# Sheet1.net
KiCad netlist of a schematic drawn in Altium Designer
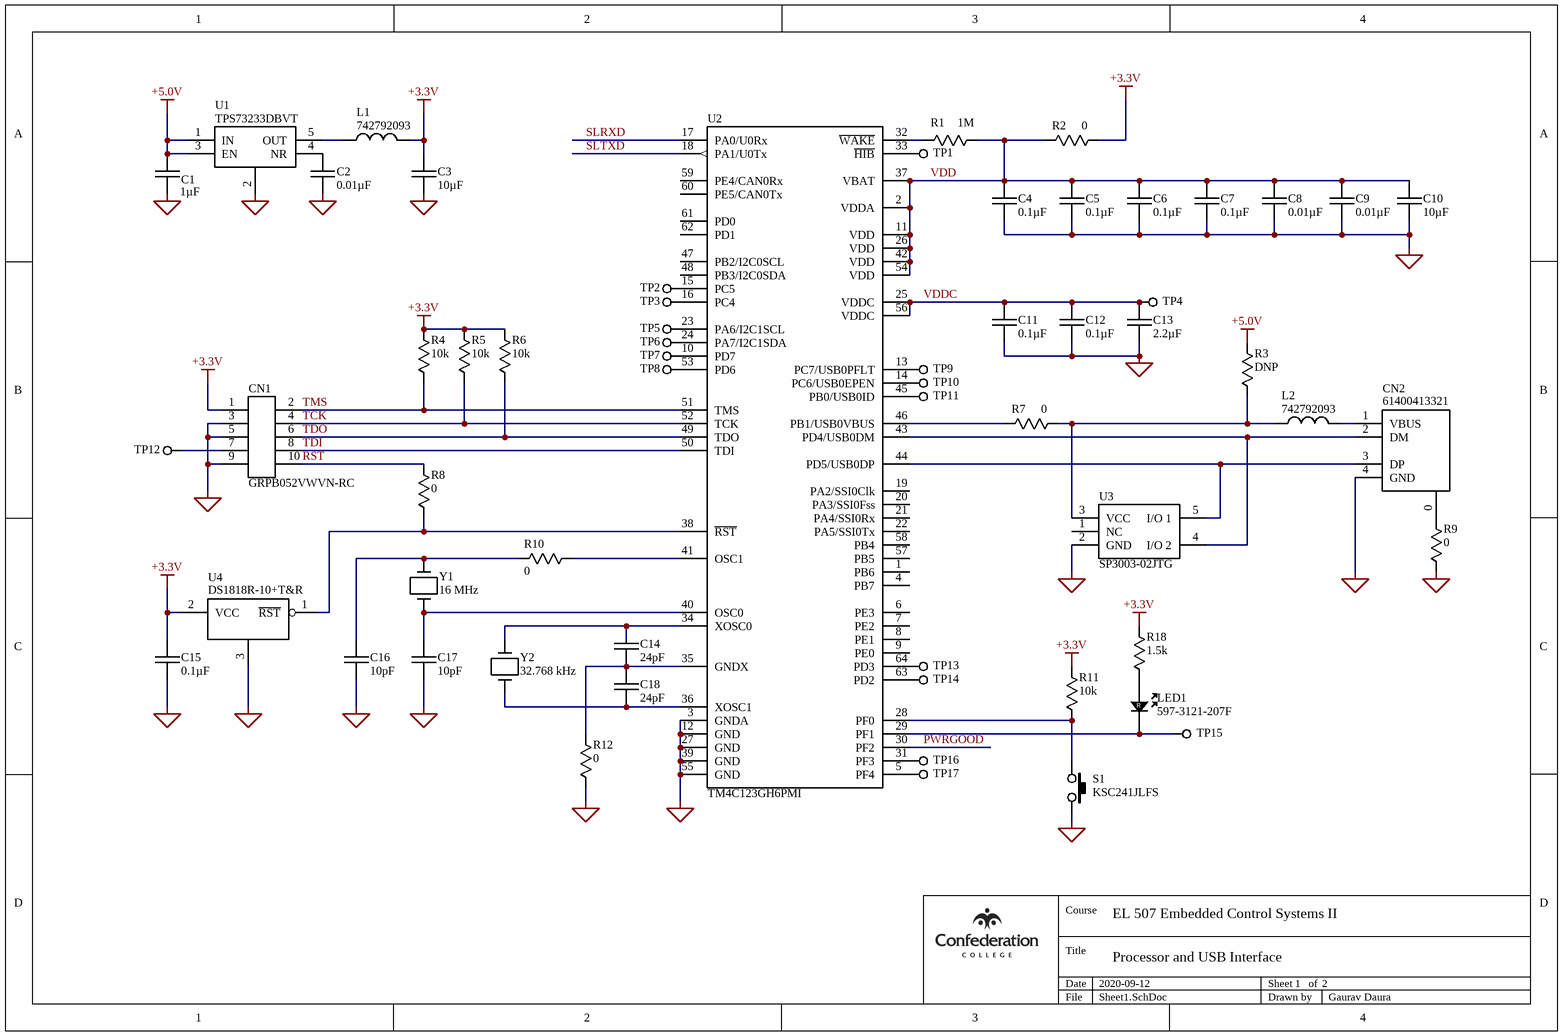
[diagram p0: Sheet1.SchDoc]

(export (version "E")
  (design (tool "Eeschema 10.0.6"))
  (components
    (comp (ref "C1")
      (value "1µF")
      (footprint "CAPC2012X135N")
      (description "1µF/50V 10% X7R Multi-Layer Ceramic Capacitor")
      (fields
        (field (name "MANUFACTURER") "Samsung Electro-Mechanics")
        (field (name "PARTNUMBER") "CL21B105KBFNNNE")
      )
      (libsource (lib "EL507-LAB001") (part "CL21B105KBFNNNE"))
    )
    (comp (ref "C2")
      (value "0.01µF")
      (footprint "CAPC2012X78N")
      (description "0.01µF/50V 10% X7R Multi-Layer Ceramic Capacitor")
      (fields
        (field (name "MANUFACTURER") "Samsung Electro-Mechanics")
        (field (name "PARTNUMBER") "CL21B103KBANNNC")
      )
      (libsource (lib "EL507-LAB001") (part "CL21B103KBANNNC"))
    )
    (comp (ref "C3")
      (value "10µF")
      (footprint "CAPC3225X250N")
      (description "10µF/50V/20% Multilayer Ceramic Chip Capacitor")
      (fields (field (name "MANUFACTURER") "Taiyo Yuden") (field (name "PARTNUMBER") "UMK325C7106MM-T"))
      (libsource (lib "EL507-LAB001") (part "UMK325C7106MM-T"))
    )
    (comp (ref "C4")
      (value "0.1µF")
      (footprint "CAPC2012X125N")
      (description "0.1µF/50V/±10% X7R Ceramic Chip Capacitor")
      (fields
        (field (name "MANUFACTURER") "Murata Manufacturing Co., Ltd.")
        (field (name "PARTNUMBER") "GRM21BR71H104KA01L")
      )
      (libsource (lib "EL507-LAB001") (part "GRM21BR71H104KA01L"))
    )
    (comp (ref "C5")
      (value "0.1µF")
      (footprint "CAPC2012X125N")
      (description "0.1µF/50V/±10% X7R Ceramic Chip Capacitor")
      (fields
        (field (name "MANUFACTURER") "Murata Manufacturing Co., Ltd.")
        (field (name "PARTNUMBER") "GRM21BR71H104KA01L")
      )
      (libsource (lib "EL507-LAB001") (part "GRM21BR71H104KA01L"))
    )
    (comp (ref "C6")
      (value "0.1µF")
      (footprint "CAPC2012X125N")
      (description "0.1µF/50V/±10% X7R Ceramic Chip Capacitor")
      (fields
        (field (name "MANUFACTURER") "Murata Manufacturing Co., Ltd.")
        (field (name "PARTNUMBER") "GRM21BR71H104KA01L")
      )
      (libsource (lib "EL507-LAB001") (part "GRM21BR71H104KA01L"))
    )
    (comp (ref "C7")
      (value "0.1µF")
      (footprint "CAPC2012X125N")
      (description "0.1µF/50V/±10% X7R Ceramic Chip Capacitor")
      (fields
        (field (name "MANUFACTURER") "Murata Manufacturing Co., Ltd.")
        (field (name "PARTNUMBER") "GRM21BR71H104KA01L")
      )
      (libsource (lib "EL507-LAB001") (part "GRM21BR71H104KA01L"))
    )
    (comp (ref "C8")
      (value "0.01µF")
      (footprint "CAPC2012X78N")
      (description "0.01µF/50V 10% X7R Multi-Layer Ceramic Capacitor")
      (fields
        (field (name "MANUFACTURER") "Samsung Electro-Mechanics")
        (field (name "PARTNUMBER") "CL21B103KBANNNC")
      )
      (libsource (lib "EL507-LAB001") (part "CL21B103KBANNNC"))
    )
    (comp (ref "C9")
      (value "0.01µF")
      (footprint "CAPC2012X78N")
      (description "0.01µF/50V 10% X7R Multi-Layer Ceramic Capacitor")
      (fields
        (field (name "MANUFACTURER") "Samsung Electro-Mechanics")
        (field (name "PARTNUMBER") "CL21B103KBANNNC")
      )
      (libsource (lib "EL507-LAB001") (part "CL21B103KBANNNC"))
    )
    (comp (ref "C10")
      (value "10µF")
      (footprint "CAPC3225X250N")
      (description "10µF/50V/20% Multilayer Ceramic Chip Capacitor")
      (fields (field (name "MANUFACTURER") "Taiyo Yuden") (field (name "PARTNUMBER") "UMK325C7106MM-T"))
      (libsource (lib "EL507-LAB001") (part "UMK325C7106MM-T"))
    )
    (comp (ref "C11")
      (value "0.1µF")
      (footprint "CAPC2012X125N")
      (description "0.1µF/50V/±10% X7R Ceramic Chip Capacitor")
      (fields
        (field (name "MANUFACTURER") "Murata Manufacturing Co., Ltd.")
        (field (name "PARTNUMBER") "GRM21BR71H104KA01L")
      )
      (libsource (lib "EL507-LAB001") (part "GRM21BR71H104KA01L"))
    )
    (comp (ref "C12")
      (value "0.1µF")
      (footprint "CAPC2012X125N")
      (description "0.1µF/50V/±10% X7R Ceramic Chip Capacitor")
      (fields
        (field (name "MANUFACTURER") "Murata Manufacturing Co., Ltd.")
        (field (name "PARTNUMBER") "GRM21BR71H104KA01L")
      )
      (libsource (lib "EL507-LAB001") (part "GRM21BR71H104KA01L"))
    )
    (comp (ref "C13")
      (value "2.2µF")
      (footprint "CAPC2012X145N")
      (description "2.2µF/50V/10% Multilayer Ceramic Chip Capacitor")
      (fields (field (name "MANUFACTURER") "Taiyo Yuden") (field (name "PARTNUMBER") "UMK212BB7225KG-T"))
      (libsource (lib "EL507-LAB001") (part "UMK212BB7225KG-T"))
    )
    (comp (ref "C14")
      (value "24pF")
      (footprint "CAPC2012X75N")
      (description "24pF/50V 5% C0G Multi-Layer Ceramic Capacitor")
      (fields
        (field (name "MANUFACTURER") "Samsung Electro-Mechanics")
        (field (name "PARTNUMBER") "CL21C240JBANNNC")
      )
      (libsource (lib "EL507-LAB001") (part "CL21C240JBANNNC"))
    )
    (comp (ref "C15")
      (value "0.1µF")
      (footprint "CAPC2012X125N")
      (description "0.1µF/50V/±10% X7R Ceramic Chip Capacitor")
      (fields
        (field (name "MANUFACTURER") "Murata Manufacturing Co., Ltd.")
        (field (name "PARTNUMBER") "GRM21BR71H104KA01L")
      )
      (libsource (lib "EL507-LAB001") (part "GRM21BR71H104KA01L"))
    )
    (comp (ref "C16")
      (value "10pF")
      (footprint "CAPC2012X94N")
      (description "10pF 100V NP0 ±10% Ceramic Capacitor")
      (fields (field (name "MANUFACTURER") "AVX Corporation") (field (name "PARTNUMBER") "08051A100KAT2A"))
      (libsource (lib "EL507-LAB001") (part "08051A100KAT2A"))
    )
    (comp (ref "C17")
      (value "10pF")
      (footprint "CAPC2012X94N")
      (description "10pF 100V NP0 ±10% Ceramic Capacitor")
      (fields (field (name "MANUFACTURER") "AVX Corporation") (field (name "PARTNUMBER") "08051A100KAT2A"))
      (libsource (lib "EL507-LAB001") (part "08051A100KAT2A"))
    )
    (comp (ref "C18")
      (value "24pF")
      (footprint "CAPC2012X75N")
      (description "24pF/50V 5% C0G Multi-Layer Ceramic Capacitor")
      (fields
        (field (name "MANUFACTURER") "Samsung Electro-Mechanics")
        (field (name "PARTNUMBER") "CL21C240JBANNNC")
      )
      (libsource (lib "EL507-LAB001") (part "CL21C240JBANNNC"))
    )
    (comp (ref "CN1")
      (value "GRPB052VWVN-RC")
      (footprint "SULLINS_GRPB052VWVN-RC")
      (description ".050\"[1.27mm] Contact Centers, Male Header")
      (fields (field (name "MANUFACTURER") "Sullins Connector Solutions, Inc."))
      (libsource (lib "EL507-LAB001") (part "GRPB052VWVN-RC"))
    )
    (comp (ref "CN2")
      (value "61400413321")
      (footprint "WURTH_61400413321")
      (description "Connector Receptacle USB Type B 4 Position Through Hole, Vertical")
      (fields (field (name "MANUFACTURER") "Wurth Elektronik GmbH & Co. KG"))
      (libsource (lib "EL507-LAB001") (part "61400413321"))
    )
    (comp (ref "L1")
      (value "742792093")
      (footprint "INDC2012X90N")
      (description "Multilayer SMD Ferrite")
      (fields (field (name "MANUFACTURER") "Wurth Elektronik GmbH & Co. KG"))
      (libsource (lib "EL507-LAB001") (part "742792093"))
    )
    (comp (ref "L2")
      (value "742792093")
      (footprint "INDC2012X90N")
      (description "Multilayer SMD Ferrite")
      (fields (field (name "MANUFACTURER") "Wurth Elektronik GmbH & Co. KG"))
      (libsource (lib "EL507-LAB001") (part "742792093"))
    )
    (comp (ref "LED1")
      (value "597-3121-207F")
      (footprint "DIALIGHT_597-3121-207F")
      (description "Micro LED, 597 Series, Red, SMD LED")
      (fields (field (name "MANUFACTURER") "Dialight Corporation"))
      (libsource (lib "EL507-LAB002") (part "597-3121-207F"))
    )
    (comp (ref "R1")
      (value "1M")
      (footprint "RESC2012X60N")
      (description "1M, 1%, 0.125W Precision Thick Film Chip Resistor")
      (fields
        (field (name "MANUFACTURER") "Panasonic Corporation of North America")
        (field (name "PARTNUMBER") "ERJ-6ENF1004V")
      )
      (libsource (lib "EL507-LAB001") (part "ERJ-6ENF1004V"))
    )
    (comp (ref "R2")
      (value "0")
      (footprint "RESC3216X60N")
      (description "0, 5%, 0.25W Thick Film Chip Resistor")
      (fields
        (field (name "MANUFACTURER") "Panasonic Corporation of North America")
        (field (name "PARTNUMBER") "ERJ-8GEY0R00V")
      )
      (libsource (lib "EL507-LAB001") (part "ERJ-8GEY0R00V"))
    )
    (comp (ref "R3")
      (value "DNP")
      (footprint "RESC2012X60N")
      (description "2012 Chip Resistor")
      (fields (field (name "MANUFACTURER") "Confederation College"))
      (libsource (lib "EL507-LAB001") (part "DNP_RESC2012X60N"))
    )
    (comp (ref "R4")
      (value "10k")
      (footprint "RESC2012X60N")
      (description "10k, 1%, 0.125W Precision Thick Film Chip Resistor")
      (fields
        (field (name "MANUFACTURER") "Panasonic Corporation of North America")
        (field (name "PARTNUMBER") "ERJ-6ENF1002V")
      )
      (libsource (lib "EL507-LAB001") (part "ERJ-6ENF1002V"))
    )
    (comp (ref "R5")
      (value "10k")
      (footprint "RESC2012X60N")
      (description "10k, 1%, 0.125W Precision Thick Film Chip Resistor")
      (fields
        (field (name "MANUFACTURER") "Panasonic Corporation of North America")
        (field (name "PARTNUMBER") "ERJ-6ENF1002V")
      )
      (libsource (lib "EL507-LAB001") (part "ERJ-6ENF1002V"))
    )
    (comp (ref "R6")
      (value "10k")
      (footprint "RESC2012X60N")
      (description "10k, 1%, 0.125W Precision Thick Film Chip Resistor")
      (fields
        (field (name "MANUFACTURER") "Panasonic Corporation of North America")
        (field (name "PARTNUMBER") "ERJ-6ENF1002V")
      )
      (libsource (lib "EL507-LAB001") (part "ERJ-6ENF1002V"))
    )
    (comp (ref "R7")
      (value "0")
      (footprint "RESC3216X60N")
      (description "0, 5%, 0.25W Thick Film Chip Resistor")
      (fields
        (field (name "MANUFACTURER") "Panasonic Corporation of North America")
        (field (name "PARTNUMBER") "ERJ-8GEY0R00V")
      )
      (libsource (lib "EL507-LAB001") (part "ERJ-8GEY0R00V"))
    )
    (comp (ref "R8")
      (value "0")
      (footprint "RESC3216X60N")
      (description "0, 5%, 0.25W Thick Film Chip Resistor")
      (fields
        (field (name "MANUFACTURER") "Panasonic Corporation of North America")
        (field (name "PARTNUMBER") "ERJ-8GEY0R00V")
      )
      (libsource (lib "EL507-LAB001") (part "ERJ-8GEY0R00V"))
    )
    (comp (ref "R9")
      (value "0")
      (footprint "RESC3216X60N")
      (description "0, 5%, 0.25W Thick Film Chip Resistor")
      (fields
        (field (name "MANUFACTURER") "Panasonic Corporation of North America")
        (field (name "PARTNUMBER") "ERJ-8GEY0R00V")
      )
      (libsource (lib "EL507-LAB001") (part "ERJ-8GEY0R00V"))
    )
    (comp (ref "R10")
      (value "0")
      (footprint "RESC3216X60N")
      (description "0, 5%, 0.25W Thick Film Chip Resistor")
      (fields
        (field (name "MANUFACTURER") "Panasonic Corporation of North America")
        (field (name "PARTNUMBER") "ERJ-8GEY0R00V")
      )
      (libsource (lib "EL507-LAB001") (part "ERJ-8GEY0R00V"))
    )
    (comp (ref "R11")
      (value "10k")
      (footprint "RESC2012X60N")
      (description "10k, 1%, 0.125W Precision Thick Film Chip Resistor")
      (fields
        (field (name "MANUFACTURER") "Panasonic Corporation of North America")
        (field (name "PARTNUMBER") "ERJ-6ENF1002V")
      )
      (libsource (lib "EL507-LAB001") (part "ERJ-6ENF1002V"))
    )
    (comp (ref "R12")
      (value "0")
      (footprint "RESC3216X60N")
      (description "0, 5%, 0.25W Thick Film Chip Resistor")
      (fields
        (field (name "MANUFACTURER") "Panasonic Corporation of North America")
        (field (name "PARTNUMBER") "ERJ-8GEY0R00V")
      )
      (libsource (lib "EL507-LAB001") (part "ERJ-8GEY0R00V"))
    )
    (comp (ref "R18")
      (value "1.5k")
      (footprint "RESC2012X60N")
      (description "1.5k, 1%, 0.125W Precision Thick Film Chip Resistor")
      (fields
        (field (name "MANUFACTURER") "Panasonic Corporation of North America")
        (field (name "PARTNUMBER") "ERJ-6ENF1501V")
      )
      (libsource (lib "EL507-LAB001") (part "ERJ-6ENF1501V"))
    )
    (comp (ref "S1")
      (value "KSC241JLFS")
      (footprint "SW_KSC241JLFS")
      (description "KSC Series Sealed Tact Switch for SMT")
      (fields (field (name "MANUFACTURER") "C&K Components"))
      (libsource (lib "EL507-LAB001") (part "KSC241JLFS"))
    )
    (comp (ref "TP1")
      (value "TESTPOINT100")
      (footprint "TP100")
      (description "Test Point")
      (fields (field (name "MANUFACTURER") "Confederation College"))
      (libsource (lib "EL507-LAB001") (part "TESTPOINT100"))
    )
    (comp (ref "TP2")
      (value "TESTPOINT100")
      (footprint "TP100")
      (description "Test Point")
      (fields (field (name "MANUFACTURER") "Confederation College"))
      (libsource (lib "EL507-LAB001") (part "TESTPOINT100"))
    )
    (comp (ref "TP3")
      (value "TESTPOINT100")
      (footprint "TP100")
      (description "Test Point")
      (fields (field (name "MANUFACTURER") "Confederation College"))
      (libsource (lib "EL507-LAB001") (part "TESTPOINT100"))
    )
    (comp (ref "TP4")
      (value "TESTPOINT100")
      (footprint "TP100")
      (description "Test Point")
      (fields (field (name "MANUFACTURER") "Confederation College"))
      (libsource (lib "EL507-LAB001") (part "TESTPOINT100"))
    )
    (comp (ref "TP5")
      (value "TESTPOINT100")
      (footprint "TP100")
      (description "Test Point")
      (fields (field (name "MANUFACTURER") "Confederation College"))
      (libsource (lib "EL507-LAB001") (part "TESTPOINT100"))
    )
    (comp (ref "TP6")
      (value "TESTPOINT100")
      (footprint "TP100")
      (description "Test Point")
      (fields (field (name "MANUFACTURER") "Confederation College"))
      (libsource (lib "EL507-LAB001") (part "TESTPOINT100"))
    )
    (comp (ref "TP7")
      (value "TESTPOINT100")
      (footprint "TP100")
      (description "Test Point")
      (fields (field (name "MANUFACTURER") "Confederation College"))
      (libsource (lib "EL507-LAB001") (part "TESTPOINT100"))
    )
    (comp (ref "TP8")
      (value "TESTPOINT100")
      (footprint "TP100")
      (description "Test Point")
      (fields (field (name "MANUFACTURER") "Confederation College"))
      (libsource (lib "EL507-LAB001") (part "TESTPOINT100"))
    )
    (comp (ref "TP9")
      (value "TESTPOINT100")
      (footprint "TP100")
      (description "Test Point")
      (fields (field (name "MANUFACTURER") "Confederation College"))
      (libsource (lib "EL507-LAB001") (part "TESTPOINT100"))
    )
    (comp (ref "TP10")
      (value "TESTPOINT100")
      (footprint "TP100")
      (description "Test Point")
      (fields (field (name "MANUFACTURER") "Confederation College"))
      (libsource (lib "EL507-LAB001") (part "TESTPOINT100"))
    )
    (comp (ref "TP11")
      (value "TESTPOINT100")
      (footprint "TP100")
      (description "Test Point")
      (fields (field (name "MANUFACTURER") "Confederation College"))
      (libsource (lib "EL507-LAB001") (part "TESTPOINT100"))
    )
    (comp (ref "TP12")
      (value "TESTPOINT100")
      (footprint "TP100")
      (description "Test Point")
      (fields (field (name "MANUFACTURER") "Confederation College"))
      (libsource (lib "EL507-LAB001") (part "TESTPOINT100"))
    )
    (comp (ref "TP13")
      (value "TESTPOINT100")
      (footprint "TP100")
      (description "Test Point")
      (fields (field (name "MANUFACTURER") "Confederation College"))
      (libsource (lib "EL507-LAB001") (part "TESTPOINT100"))
    )
    (comp (ref "TP14")
      (value "TESTPOINT100")
      (footprint "TP100")
      (description "Test Point")
      (fields (field (name "MANUFACTURER") "Confederation College"))
      (libsource (lib "EL507-LAB001") (part "TESTPOINT100"))
    )
    (comp (ref "TP15")
      (value "TESTPOINT100")
      (footprint "TP100")
      (description "Test Point")
      (fields (field (name "MANUFACTURER") "Confederation College"))
      (libsource (lib "EL507-LAB001") (part "TESTPOINT100"))
    )
    (comp (ref "TP16")
      (value "TESTPOINT100")
      (footprint "TP100")
      (description "Test Point")
      (fields (field (name "MANUFACTURER") "Confederation College"))
      (libsource (lib "EL507-LAB001") (part "TESTPOINT100"))
    )
    (comp (ref "TP17")
      (value "TESTPOINT100")
      (footprint "TP100")
      (description "Test Point")
      (fields (field (name "MANUFACTURER") "Confederation College"))
      (libsource (lib "EL507-LAB001") (part "TESTPOINT100"))
    )
    (comp (ref "U1")
      (value "TPS73233DBVT")
      (footprint "SOT95P280X145-5N")
      (description "250 mA, 3.3V Low Dropout Voltage Regulator")
      (fields (field (name "MANUFACTURER") "Texas Instruments, Inc."))
      (libsource (lib "EL507-LAB001") (part "TPS73233DBVT"))
    )
    (comp (ref "U2")
      (value "TM4C123GH6PMI")
      (footprint "QFP50P1200X1200X140-64N")
      (description "Tiva TM4C123GH6PM Microcontroller")
      (fields (field (name "MANUFACTURER") "Texas Instruments, Inc."))
      (libsource (lib "EL507-LAB001") (part "TM4C123GH6PMI"))
    )
    (comp (ref "U3")
      (value "SP3003-02JTG")
      (footprint "SOT65P220X90-5N")
      (description "TVS Diode Array - Low Capacitance ESD Protection")
      (fields (field (name "MANUFACTURER") "Littelfuse, Inc."))
      (libsource (lib "EL507-LAB001") (part "SP3003-02JTG"))
    )
    (comp (ref "U4")
      (value "DS1818R-10+T&R")
      (footprint "SOT95P235X100-3N")
      (description "3.3 V EconoReset with Pushbutton")
      (fields (field (name "MANUFACTURER") "Maxim Integrated"))
      (libsource (lib "EL507-LAB001") (part "DS1818R-10+T&R"))
    )
    (comp (ref "Y1")
      (value "16 MHz")
      (footprint "XTAL500X320X130")
      (description "16 MHz Miniature Ceramic SMD Crystal")
      (fields
        (field (name "PARTNUMBER") "ABM3-16.000MHZ-B2-T")
        (field (name "MANUFACTURER") "Abracon Corporation")
      )
      (libsource (lib "EL507-LAB001") (part "ABM3-16.000MHZ-B2-T"))
    )
    (comp (ref "Y2")
      (value "32.768 kHz")
      (footprint "ABRACON_AB26TRB-32.768KHZ-T")
      (description "32.768 kHz Radial Can Crystal")
      (fields
        (field (name "PARTNUMBER") "AB26TRB-32.768KHZ-T")
        (field (name "MANUFACTURER") "Abracon Corporation")
      )
      (libsource (lib "EL507-LAB001") (part "AB26TRB-32.768KHZ-T"))
    )
  )
  (nets
    (net (code "1") (name "+3.3V") (class "Default")
      (node (ref "C15") (pin "1") (pinfunction "1_1") (pintype "passive"))
      (node (ref "C3") (pin "1") (pinfunction "1_1") (pintype "passive"))
      (node (ref "CN1") (pin "1") (pinfunction "1_1") (pintype "passive"))
      (node (ref "L1") (pin "2") (pinfunction "2_2") (pintype "passive"))
      (node (ref "R11") (pin "2") (pinfunction "2_2") (pintype "passive"))
      (node (ref "R18") (pin "2") (pinfunction "2_2") (pintype "passive"))
      (node (ref "R2") (pin "2") (pinfunction "2_2") (pintype "passive"))
      (node (ref "R4") (pin "2") (pinfunction "2_2") (pintype "passive"))
      (node (ref "R5") (pin "2") (pinfunction "2_2") (pintype "passive"))
      (node (ref "R6") (pin "2") (pinfunction "2_2") (pintype "passive"))
      (node (ref "U4") (pin "2") (pinfunction "VCC_2") (pintype "power_in"))
    )
    (net (code "2") (name "+5.0V") (class "Default")
      (node (ref "C1") (pin "1") (pinfunction "1_1") (pintype "passive"))
      (node (ref "R3") (pin "2") (pinfunction "2_2") (pintype "passive"))
      (node (ref "U1") (pin "1") (pinfunction "IN_1") (pintype "passive"))
      (node (ref "U1") (pin "3") (pinfunction "EN_3") (pintype "passive"))
    )
    (net (code "3") (name "/PWRGOOD") (class "Default")
      (node (ref "U2") (pin "30") (pinfunction "PF2_30") (pintype "passive"))
    )
    (net (code "4") (name "/RST") (class "Default")
      (node (ref "CN1") (pin "10") (pinfunction "10_10") (pintype "passive"))
      (node (ref "R8") (pin "2") (pinfunction "2_2") (pintype "passive"))
    )
    (net (code "5") (name "/SLRXD") (class "Default")
      (node (ref "U2") (pin "17") (pinfunction "PA0/U0Rx_17") (pintype "passive"))
    )
    (net (code "6") (name "/SLTXD") (class "Default")
      (node (ref "U2") (pin "18") (pinfunction "PA1/U0Tx_18") (pintype "output"))
    )
    (net (code "7") (name "/TCK") (class "Default")
      (node (ref "CN1") (pin "4") (pinfunction "4_4") (pintype "passive"))
      (node (ref "R5") (pin "1") (pinfunction "1_1") (pintype "passive"))
      (node (ref "U2") (pin "52") (pinfunction "TCK_52") (pintype "passive"))
    )
    (net (code "8") (name "/TDI") (class "Default")
      (node (ref "CN1") (pin "8") (pinfunction "8_8") (pintype "passive"))
      (node (ref "U2") (pin "50") (pinfunction "TDI_50") (pintype "passive"))
    )
    (net (code "9") (name "/TDO") (class "Default")
      (node (ref "CN1") (pin "6") (pinfunction "6_6") (pintype "passive"))
      (node (ref "R6") (pin "1") (pinfunction "1_1") (pintype "passive"))
      (node (ref "U2") (pin "49") (pinfunction "TDO_49") (pintype "passive"))
    )
    (net (code "10") (name "/TMS") (class "Default")
      (node (ref "CN1") (pin "2") (pinfunction "2_2") (pintype "passive"))
      (node (ref "R4") (pin "1") (pinfunction "1_1") (pintype "passive"))
      (node (ref "U2") (pin "51") (pinfunction "TMS_51") (pintype "passive"))
    )
    (net (code "11") (name "/VDD") (class "Default")
      (node (ref "C10") (pin "2") (pinfunction "2_2") (pintype "passive"))
      (node (ref "C4") (pin "2") (pinfunction "2_2") (pintype "passive"))
      (node (ref "C5") (pin "2") (pinfunction "2_2") (pintype "passive"))
      (node (ref "C6") (pin "2") (pinfunction "2_2") (pintype "passive"))
      (node (ref "C7") (pin "2") (pinfunction "2_2") (pintype "passive"))
      (node (ref "C8") (pin "2") (pinfunction "2_2") (pintype "passive"))
      (node (ref "C9") (pin "2") (pinfunction "2_2") (pintype "passive"))
      (node (ref "R1") (pin "2") (pinfunction "2_2") (pintype "passive"))
      (node (ref "R2") (pin "1") (pinfunction "1_1") (pintype "passive"))
      (node (ref "U2") (pin "11") (pinfunction "VDD_11") (pintype "power_in"))
      (node (ref "U2") (pin "2") (pinfunction "VDDA_2") (pintype "power_in"))
      (node (ref "U2") (pin "26") (pinfunction "VDD_26") (pintype "passive"))
      (node (ref "U2") (pin "37") (pinfunction "VBAT_37") (pintype "passive"))
      (node (ref "U2") (pin "42") (pinfunction "VDD_42") (pintype "passive"))
      (node (ref "U2") (pin "54") (pinfunction "VDD_54") (pintype "power_in"))
    )
    (net (code "12") (name "/VDDC") (class "Default")
      (node (ref "C11") (pin "2") (pinfunction "2_2") (pintype "passive"))
      (node (ref "C12") (pin "2") (pinfunction "2_2") (pintype "passive"))
      (node (ref "C13") (pin "1") (pinfunction "1_1") (pintype "passive"))
      (node (ref "TP4") (pin "1") (pintype "passive"))
      (node (ref "U2") (pin "25") (pinfunction "VDDC_25") (pintype "passive"))
      (node (ref "U2") (pin "56") (pinfunction "VDDC_56") (pintype "power_in"))
    )
    (net (code "13") (name "GND") (class "Default")
      (node (ref "C1") (pin "2") (pinfunction "2_2") (pintype "passive"))
      (node (ref "C10") (pin "1") (pinfunction "1_1") (pintype "passive"))
      (node (ref "C11") (pin "1") (pinfunction "1_1") (pintype "passive"))
      (node (ref "C12") (pin "1") (pinfunction "1_1") (pintype "passive"))
      (node (ref "C13") (pin "2") (pinfunction "2_2") (pintype "passive"))
      (node (ref "C15") (pin "2") (pinfunction "2_2") (pintype "passive"))
      (node (ref "C16") (pin "2") (pinfunction "2_2") (pintype "passive"))
      (node (ref "C17") (pin "2") (pinfunction "2_2") (pintype "passive"))
      (node (ref "C2") (pin "2") (pinfunction "2_2") (pintype "passive"))
      (node (ref "C3") (pin "2") (pinfunction "2_2") (pintype "passive"))
      (node (ref "C4") (pin "1") (pinfunction "1_1") (pintype "passive"))
      (node (ref "C5") (pin "1") (pinfunction "1_1") (pintype "passive"))
      (node (ref "C6") (pin "1") (pinfunction "1_1") (pintype "passive"))
      (node (ref "C7") (pin "1") (pinfunction "1_1") (pintype "passive"))
      (node (ref "C8") (pin "1") (pinfunction "1_1") (pintype "passive"))
      (node (ref "C9") (pin "1") (pinfunction "1_1") (pintype "passive"))
      (node (ref "CN1") (pin "3") (pinfunction "3_3") (pintype "passive"))
      (node (ref "CN1") (pin "5") (pinfunction "5_5") (pintype "passive"))
      (node (ref "CN1") (pin "9") (pinfunction "9_9") (pintype "passive"))
      (node (ref "CN2") (pin "4") (pinfunction "GND_4") (pintype "passive"))
      (node (ref "R12") (pin "1") (pinfunction "1_1") (pintype "passive"))
      (node (ref "R9") (pin "1") (pinfunction "1_1") (pintype "passive"))
      (node (ref "S1") (pin "1") (pinfunction "1_1") (pintype "passive"))
      (node (ref "U1") (pin "2") (pinfunction "GND_2") (pintype "passive"))
      (node (ref "U2") (pin "12") (pinfunction "GND_12") (pintype "power_in"))
      (node (ref "U2") (pin "27") (pinfunction "GND_27") (pintype "passive"))
      (node (ref "U2") (pin "3") (pinfunction "GNDA_3") (pintype "power_in"))
      (node (ref "U2") (pin "39") (pinfunction "GND_39") (pintype "power_in"))
      (node (ref "U2") (pin "55") (pinfunction "GND_55") (pintype "power_in"))
      (node (ref "U3") (pin "2") (pinfunction "GND_2") (pintype "passive"))
      (node (ref "U4") (pin "3") (pinfunction "GND_3") (pintype "power_in"))
    )
    (net (code "14") (name "Net-(C16-Pad1)") (class "Default")
      (node (ref "C16") (pin "1") (pinfunction "1_1") (pintype "passive"))
      (node (ref "R10") (pin "1") (pinfunction "1_1") (pintype "passive"))
      (node (ref "Y1") (pin "2") (pinfunction "2_2") (pintype "passive"))
    )
    (net (code "15") (name "Net-(CN1-Pad7)") (class "Default")
      (node (ref "CN1") (pin "7") (pinfunction "7_7") (pintype "passive"))
      (node (ref "TP12") (pin "1") (pintype "passive"))
    )
    (net (code "16") (name "Net-(CN2-DM)") (class "Default")
      (node (ref "CN2") (pin "2") (pinfunction "DM_2") (pintype "passive"))
      (node (ref "U2") (pin "43") (pinfunction "PD4/USB0DM_43") (pintype "passive"))
      (node (ref "U3") (pin "4") (pinfunction "I/O_2_4") (pintype "passive"))
    )
    (net (code "17") (name "Net-(CN2-DP)") (class "Default")
      (node (ref "CN2") (pin "3") (pinfunction "DP_3") (pintype "passive"))
      (node (ref "U2") (pin "44") (pinfunction "PD5/USB0DP_44") (pintype "passive"))
      (node (ref "U3") (pin "5") (pinfunction "I/O_1_5") (pintype "passive"))
    )
    (net (code "18") (name "Net-(CN2-Pad0)") (class "Default")
      (node (ref "CN2") (pin "0") (pinfunction "0_0") (pintype "passive"))
      (node (ref "R9") (pin "2") (pinfunction "2_2") (pintype "passive"))
    )
    (net (code "19") (name "Net-(CN2-VBUS)") (class "Default")
      (node (ref "CN2") (pin "1") (pinfunction "VBUS_1") (pintype "passive"))
      (node (ref "L2") (pin "2") (pinfunction "2_2") (pintype "passive"))
    )
    (net (code "20") (name "Net-(LED1-A)") (class "Default")
      (node (ref "LED1") (pin "2") (pinfunction "A_2") (pintype "passive"))
      (node (ref "R18") (pin "1") (pinfunction "1_1") (pintype "passive"))
    )
    (net (code "21") (name "Net-(LED1-K)") (class "Default")
      (node (ref "LED1") (pin "1") (pinfunction "K_1") (pintype "passive"))
      (node (ref "TP15") (pin "1") (pintype "passive"))
      (node (ref "U2") (pin "29") (pinfunction "PF1_29") (pintype "passive"))
    )
    (net (code "22") (name "Net-(U1-NR)") (class "Default")
      (node (ref "C2") (pin "1") (pinfunction "1_1") (pintype "passive"))
      (node (ref "U1") (pin "4") (pinfunction "NR_4") (pintype "passive"))
    )
    (net (code "23") (name "Net-(U1-OUT)") (class "Default")
      (node (ref "L1") (pin "1") (pinfunction "1_1") (pintype "passive"))
      (node (ref "U1") (pin "5") (pinfunction "OUT_5") (pintype "passive"))
    )
    (net (code "24") (name "Net-(U2-GNDX)") (class "Default")
      (node (ref "C14") (pin "2") (pinfunction "2_2") (pintype "passive"))
      (node (ref "C18") (pin "1") (pinfunction "1_1") (pintype "passive"))
      (node (ref "R12") (pin "2") (pinfunction "2_2") (pintype "passive"))
      (node (ref "U2") (pin "35") (pinfunction "GNDX_35") (pintype "power_in"))
    )
    (net (code "25") (name "Net-(U2-OSC0)") (class "Default")
      (node (ref "C17") (pin "1") (pinfunction "1_1") (pintype "passive"))
      (node (ref "U2") (pin "40") (pinfunction "OSC0_40") (pintype "power_in"))
      (node (ref "Y1") (pin "1") (pinfunction "1_1") (pintype "passive"))
    )
    (net (code "26") (name "Net-(U2-OSC1)") (class "Default")
      (node (ref "R10") (pin "2") (pinfunction "2_2") (pintype "passive"))
      (node (ref "U2") (pin "41") (pinfunction "OSC1_41") (pintype "power_in"))
    )
    (net (code "27") (name "Net-(U2-PA6{slash}I2C1SCL)") (class "Default")
      (node (ref "TP5") (pin "1") (pintype "passive"))
      (node (ref "U2") (pin "23") (pinfunction "PA6/I2C1SCL_23") (pintype "passive"))
    )
    (net (code "28") (name "Net-(U2-PA7{slash}I2C1SDA)") (class "Default")
      (node (ref "TP6") (pin "1") (pintype "passive"))
      (node (ref "U2") (pin "24") (pinfunction "PA7/I2C1SDA_24") (pintype "passive"))
    )
    (net (code "29") (name "Net-(U2-PB0{slash}USB0ID)") (class "Default")
      (node (ref "TP11") (pin "1") (pintype "passive"))
      (node (ref "U2") (pin "45") (pinfunction "PB0/USB0ID_45") (pintype "passive"))
    )
    (net (code "30") (name "Net-(U2-PB1{slash}USB0VBUS)") (class "Default")
      (node (ref "R7") (pin "1") (pinfunction "1_1") (pintype "passive"))
      (node (ref "U2") (pin "46") (pinfunction "PB1/USB0VBUS_46") (pintype "passive"))
    )
    (net (code "31") (name "Net-(U2-PC4)") (class "Default")
      (node (ref "TP3") (pin "1") (pintype "passive"))
      (node (ref "U2") (pin "16") (pinfunction "PC4_16") (pintype "passive"))
    )
    (net (code "32") (name "Net-(U2-PC5)") (class "Default")
      (node (ref "TP2") (pin "1") (pintype "passive"))
      (node (ref "U2") (pin "15") (pinfunction "PC5_15") (pintype "passive"))
    )
    (net (code "33") (name "Net-(U2-PC6{slash}USB0EPEN)") (class "Default")
      (node (ref "TP10") (pin "1") (pintype "passive"))
      (node (ref "U2") (pin "14") (pinfunction "PC6/USB0EPEN_14") (pintype "passive"))
    )
    (net (code "34") (name "Net-(U2-PC7{slash}USB0PFLT)") (class "Default")
      (node (ref "TP9") (pin "1") (pintype "passive"))
      (node (ref "U2") (pin "13") (pinfunction "PC7/USB0PFLT_13") (pintype "passive"))
    )
    (net (code "35") (name "Net-(U2-PD2)") (class "Default")
      (node (ref "TP14") (pin "1") (pintype "passive"))
      (node (ref "U2") (pin "63") (pinfunction "PD2_63") (pintype "passive"))
    )
    (net (code "36") (name "Net-(U2-PD3)") (class "Default")
      (node (ref "TP13") (pin "1") (pintype "passive"))
      (node (ref "U2") (pin "64") (pinfunction "PD3_64") (pintype "passive"))
    )
    (net (code "37") (name "Net-(U2-PD6)") (class "Default")
      (node (ref "TP8") (pin "1") (pintype "passive"))
      (node (ref "U2") (pin "53") (pinfunction "PD6_53") (pintype "passive"))
    )
    (net (code "38") (name "Net-(U2-PD7)") (class "Default")
      (node (ref "TP7") (pin "1") (pintype "passive"))
      (node (ref "U2") (pin "10") (pinfunction "PD7_10") (pintype "passive"))
    )
    (net (code "39") (name "Net-(U2-PF0)") (class "Default")
      (node (ref "R11") (pin "1") (pinfunction "1_1") (pintype "passive"))
      (node (ref "S1") (pin "2") (pinfunction "2_2") (pintype "passive"))
      (node (ref "U2") (pin "28") (pinfunction "PF0_28") (pintype "passive"))
    )
    (net (code "40") (name "Net-(U2-PF3)") (class "Default")
      (node (ref "TP16") (pin "1") (pintype "passive"))
      (node (ref "U2") (pin "31") (pinfunction "PF3_31") (pintype "passive"))
    )
    (net (code "41") (name "Net-(U2-PF4)") (class "Default")
      (node (ref "TP17") (pin "1") (pintype "passive"))
      (node (ref "U2") (pin "5") (pinfunction "PF4_5") (pintype "passive"))
    )
    (net (code "42") (name "Net-(U2-XOSC0)") (class "Default")
      (node (ref "C14") (pin "1") (pinfunction "1_1") (pintype "passive"))
      (node (ref "U2") (pin "34") (pinfunction "XOSC0_34") (pintype "passive"))
      (node (ref "Y2") (pin "2") (pinfunction "2_2") (pintype "passive"))
    )
    (net (code "43") (name "Net-(U2-XOSC1)") (class "Default")
      (node (ref "C18") (pin "2") (pinfunction "2_2") (pintype "passive"))
      (node (ref "U2") (pin "36") (pinfunction "XOSC1_36") (pintype "passive"))
      (node (ref "Y2") (pin "1") (pinfunction "1_1") (pintype "passive"))
    )
    (net (code "44") (name "Net-(U2-~{HIB})") (class "Default")
      (node (ref "TP1") (pin "1") (pintype "passive"))
      (node (ref "U2") (pin "33") (pinfunction "~{HIB}_33") (pintype "passive"))
    )
    (net (code "45") (name "Net-(U2-~{RST})") (class "Default")
      (node (ref "R8") (pin "1") (pinfunction "1_1") (pintype "passive"))
      (node (ref "U2") (pin "38") (pinfunction "~{RST}_38") (pintype "passive"))
      (node (ref "U4") (pin "1") (pinfunction "~{RST}_1") (pintype "open_collector"))
    )
    (net (code "46") (name "Net-(U2-~{WAKE})") (class "Default")
      (node (ref "R1") (pin "1") (pinfunction "1_1") (pintype "passive"))
      (node (ref "U2") (pin "32") (pinfunction "~{WAKE}_32") (pintype "passive"))
    )
    (net (code "47") (name "Net-(U3-VCC)") (class "Default")
      (node (ref "L2") (pin "1") (pinfunction "1_1") (pintype "passive"))
      (node (ref "R3") (pin "1") (pinfunction "1_1") (pintype "passive"))
      (node (ref "R7") (pin "2") (pinfunction "2_2") (pintype "passive"))
      (node (ref "U3") (pin "3") (pinfunction "VCC_3") (pintype "passive"))
    )
    (net (code "48") (name "unconnected-(U2-PA2{slash}SSI0Clk-Pad19)") (class "Default")
      (node (ref "U2") (pin "19") (pinfunction "PA2/SSI0Clk_19") (pintype "passive"))
    )
    (net (code "49") (name "unconnected-(U2-PA3{slash}SSI0Fss-Pad20)") (class "Default")
      (node (ref "U2") (pin "20") (pinfunction "PA3/SSI0Fss_20") (pintype "passive"))
    )
    (net (code "50") (name "unconnected-(U2-PA4{slash}SSI0Rx-Pad21)") (class "Default")
      (node (ref "U2") (pin "21") (pinfunction "PA4/SSI0Rx_21") (pintype "passive"))
    )
    (net (code "51") (name "unconnected-(U2-PA5{slash}SSI0Tx-Pad22)") (class "Default")
      (node (ref "U2") (pin "22") (pinfunction "PA5/SSI0Tx_22") (pintype "passive"))
    )
    (net (code "52") (name "unconnected-(U2-PB2{slash}I2C0SCL-Pad47)") (class "Default")
      (node (ref "U2") (pin "47") (pinfunction "PB2/I2C0SCL_47") (pintype "passive"))
    )
    (net (code "53") (name "unconnected-(U2-PB3{slash}I2C0SDA-Pad48)") (class "Default")
      (node (ref "U2") (pin "48") (pinfunction "PB3/I2C0SDA_48") (pintype "passive"))
    )
    (net (code "54") (name "unconnected-(U2-PB4-Pad58)") (class "Default")
      (node (ref "U2") (pin "58") (pinfunction "PB4_58") (pintype "passive"))
    )
    (net (code "55") (name "unconnected-(U2-PB5-Pad57)") (class "Default")
      (node (ref "U2") (pin "57") (pinfunction "PB5_57") (pintype "passive"))
    )
    (net (code "56") (name "unconnected-(U2-PB6-Pad1)") (class "Default")
      (node (ref "U2") (pin "1") (pinfunction "PB6_1") (pintype "passive"))
    )
    (net (code "57") (name "unconnected-(U2-PB7-Pad4)") (class "Default")
      (node (ref "U2") (pin "4") (pinfunction "PB7_4") (pintype "passive"))
    )
    (net (code "58") (name "unconnected-(U2-PD0-Pad61)") (class "Default")
      (node (ref "U2") (pin "61") (pinfunction "PD0_61") (pintype "passive"))
    )
    (net (code "59") (name "unconnected-(U2-PD1-Pad62)") (class "Default")
      (node (ref "U2") (pin "62") (pinfunction "PD1_62") (pintype "passive"))
    )
    (net (code "60") (name "unconnected-(U2-PE0-Pad9)") (class "Default")
      (node (ref "U2") (pin "9") (pinfunction "PE0_9") (pintype "passive"))
    )
    (net (code "61") (name "unconnected-(U2-PE1-Pad8)") (class "Default")
      (node (ref "U2") (pin "8") (pinfunction "PE1_8") (pintype "passive"))
    )
    (net (code "62") (name "unconnected-(U2-PE2-Pad7)") (class "Default")
      (node (ref "U2") (pin "7") (pinfunction "PE2_7") (pintype "passive"))
    )
    (net (code "63") (name "unconnected-(U2-PE3-Pad6)") (class "Default")
      (node (ref "U2") (pin "6") (pinfunction "PE3_6") (pintype "passive"))
    )
    (net (code "64") (name "unconnected-(U2-PE4{slash}CAN0Rx-Pad59)") (class "Default")
      (node (ref "U2") (pin "59") (pinfunction "PE4/CAN0Rx_59") (pintype "passive"))
    )
    (net (code "65") (name "unconnected-(U2-PE5{slash}CAN0Tx-Pad60)") (class "Default")
      (node (ref "U2") (pin "60") (pinfunction "PE5/CAN0Tx_60") (pintype "passive"))
    )
    (net (code "66") (name "unconnected-(U3-NC-Pad1)") (class "Default")
      (node (ref "U3") (pin "1") (pinfunction "NC_1") (pintype "passive"))
    )
  )
)
